# aKaReZa75_eBoard_STM32F103C8__STM32F103C.net
KiCad netlist of a schematic drawn in Altium Designer
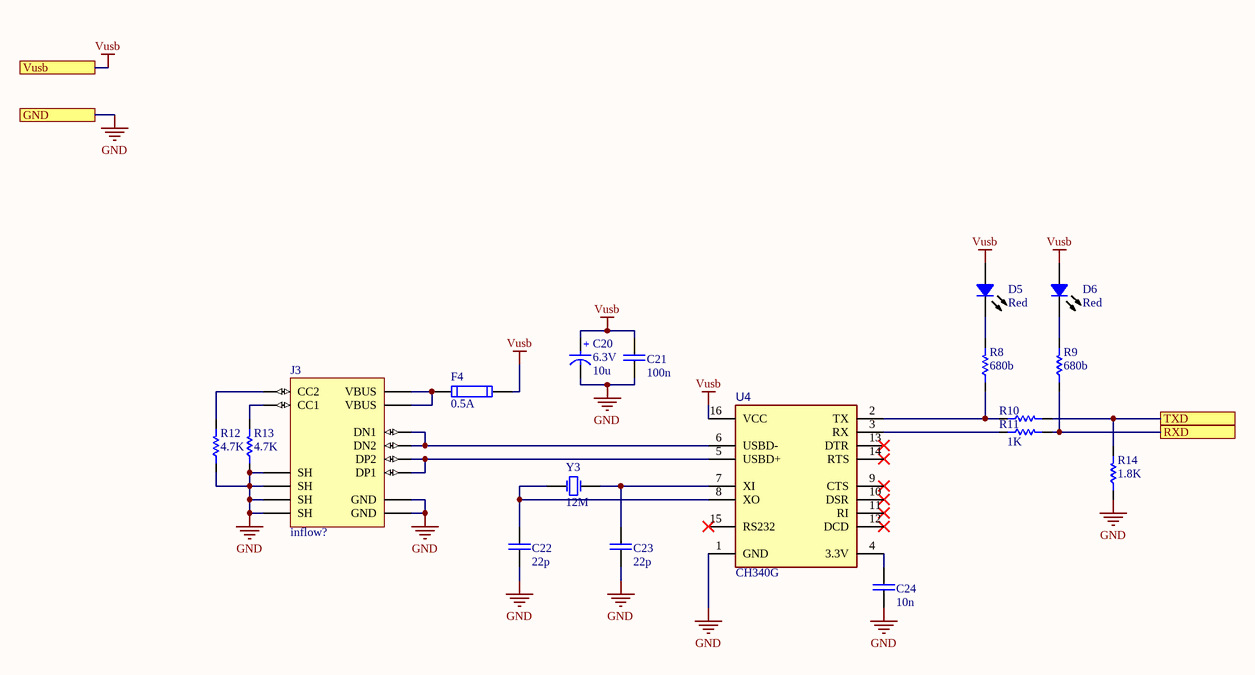
[diagram p0: aKaReZa75_eBoard_STM32F103C8__STM32F103C8__USBtoTTL.SchDoc]

(export (version "E")
  (design (tool "Eeschema 10.0.6"))
  (components
    (comp (ref "C20")
      (value "10u")
      (footprint "SMT_C_Tantalum_A")
      (description "Tantalum Capacitor,TAJ Series-SMD")
      (fields (field (name "RATING") "6.3V") (field (name "VALIDATION") "Valid"))
      (libsource (lib "aKaReZa") (part "Cap_Tantalum"))
    )
    (comp (ref "C21")
      (value "100n")
      (footprint "CAP 0805/2012")
      (description "Bipolar ceramic capacitor SMD")
      (fields (field (name "VALIDATION") "Valid"))
      (libsource (lib "aKaReZa") (part "Cap_Multi_SMD_100nF_0805"))
    )
    (comp (ref "C22")
      (value "22p")
      (footprint "CAP 0805/2012")
      (description "Bipolar ceramic capacitor SMD")
      (fields (field (name "VALIDATION") "Valid"))
      (libsource (lib "aKaReZa") (part "Cap_Multi_SMD_0805"))
    )
    (comp (ref "C23")
      (value "22p")
      (footprint "CAP 0805/2012")
      (description "Bipolar ceramic capacitor SMD")
      (fields (field (name "VALIDATION") "Valid"))
      (libsource (lib "aKaReZa") (part "Cap_Multi_SMD_0805"))
    )
    (comp (ref "C24")
      (value "10n")
      (footprint "CAP 0805/2012")
      (description "Bipolar ceramic capacitor SMD")
      (fields (field (name "VALIDATION") "Valid"))
      (libsource (lib "aKaReZa") (part "Cap_Multi_SMD_0805"))
    )
    (comp (ref "D5")
      (value "Red")
      (footprint "LED 0805/2012 RED")
      (description "LED")
      (fields (field (name "VALIDATION") "Valid"))
      (libsource (lib "aKaReZa") (part "Semi_LED_SMD"))
    )
    (comp (ref "D6")
      (value "Red")
      (footprint "LED 0805/2012 RED")
      (description "LED")
      (fields (field (name "VALIDATION") "Valid"))
      (libsource (lib "aKaReZa") (part "Semi_LED_SMD"))
    )
    (comp (ref "F4")
      (value "0.5A")
      (footprint "1206_F")
      (description "Short circiut  protection")
      (fields (field (name "VALIDATION") "Valid"))
      (libsource (lib "aKaReZa") (part "Other_Elec_Fuse_SMD"))
    )
    (comp (ref "J3")
      (value "12b")
      (footprint "HRO_TYPE-C-31-M-12 - Extended")
      (description "USB C Female Connector")
      (fields (field (name "INFLOW") "inflow?") (field (name "VALIDATION") "Valid"))
      (libsource (lib "aKaReZa") (part "Con_USB_C"))
    )
    (comp (ref "R8")
      (value "680b")
      (footprint "RES 0805 (2012X06L)")
      (description "Resistor")
      (fields (field (name "VALIDATION") "Valid"))
      (libsource (lib "aKaReZa") (part "Res_SMD_0805"))
    )
    (comp (ref "R9")
      (value "680b")
      (footprint "RES 0805 (2012X06L)")
      (description "Resistor")
      (fields (field (name "VALIDATION") "Valid"))
      (libsource (lib "aKaReZa") (part "Res_SMD_0805"))
    )
    (comp (ref "R10")
      (value "1K")
      (footprint "RES 0805 (2012X06L)")
      (description "Resistor")
      (fields (field (name "VALIDATION") "Valid"))
      (libsource (lib "aKaReZa") (part "Res_SMD_0805"))
    )
    (comp (ref "R11")
      (value "1K")
      (footprint "RES 0805 (2012X06L)")
      (description "Resistor")
      (fields (field (name "VALIDATION") "Valid"))
      (libsource (lib "aKaReZa") (part "Res_SMD_0805"))
    )
    (comp (ref "R12")
      (value "4.7K")
      (footprint "RES 0805 (2012X06L)")
      (description "Resistor")
      (fields (field (name "VALIDATION") "Valid"))
      (libsource (lib "aKaReZa") (part "Res_SMD_0805"))
    )
    (comp (ref "R13")
      (value "4.7K")
      (footprint "RES 0805 (2012X06L)")
      (description "Resistor")
      (fields (field (name "VALIDATION") "Valid"))
      (libsource (lib "aKaReZa") (part "Res_SMD_0805"))
    )
    (comp (ref "R14")
      (value "1.8K")
      (footprint "RES 0805 (2012X06L)")
      (description "Resistor")
      (fields (field (name "VALIDATION") "Valid"))
      (libsource (lib "aKaReZa") (part "Res_SMD_0805"))
    )
    (comp (ref "U4")
      (value "CH340G")
      (footprint "SO16_M")
      (description "TTL To USB Chip")
      (fields (field (name "VALIDATION") "Valid"))
      (libsource (lib "aKaReZa") (part "IC_Converter_CH340G"))
    )
    (comp (ref "Y3")
      (value "12M")
      (footprint "Crystal SMD")
      (description "Crystal Oscillator")
      (fields (field (name "VALIDATION") "Valid"))
      (libsource (lib "aKaReZa") (part "Other_Elec_Xtal_SMD"))
    )
  )
  (nets
    (net (code "1") (name "/RXD") (class "Default")
      (node (ref "R11") (pin "2") (pinfunction "2_2") (pintype "passive"))
      (node (ref "R9") (pin "1") (pinfunction "1_1") (pintype "passive"))
    )
    (net (code "2") (name "/TXD") (class "Default")
      (node (ref "R10") (pin "2") (pinfunction "2_2") (pintype "passive"))
      (node (ref "R14") (pin "2") (pinfunction "2_2") (pintype "passive"))
    )
    (net (code "3") (name "GND") (class "Default")
      (node (ref "C20") (pin "2") (pinfunction "-_2") (pintype "passive"))
      (node (ref "C21") (pin "2") (pinfunction "2_2") (pintype "passive"))
      (node (ref "C22") (pin "2") (pinfunction "2_2") (pintype "passive"))
      (node (ref "C23") (pin "2") (pinfunction "2_2") (pintype "passive"))
      (node (ref "C24") (pin "2") (pinfunction "2_2") (pintype "passive"))
      (node (ref "J3") (pin "A1_B12") (pinfunction "GND_A1_B12") (pintype "power_in"))
      (node (ref "J3") (pin "B1_A12") (pinfunction "GND_B1_A12") (pintype "power_in"))
      (node (ref "J3") (pin "S1") (pinfunction "SH_S1") (pintype "passive"))
      (node (ref "J3") (pin "S2") (pinfunction "SH_S2") (pintype "passive"))
      (node (ref "J3") (pin "S3") (pinfunction "SH_S3") (pintype "passive"))
      (node (ref "J3") (pin "S4") (pinfunction "SH_S4") (pintype "passive"))
      (node (ref "R12") (pin "1") (pinfunction "1_1") (pintype "passive"))
      (node (ref "R13") (pin "1") (pinfunction "1_1") (pintype "passive"))
      (node (ref "R14") (pin "1") (pinfunction "1_1") (pintype "passive"))
      (node (ref "U4") (pin "1") (pinfunction "GND_1") (pintype "passive"))
    )
    (net (code "4") (name "Net-(D5-Pad2)") (class "Default")
      (node (ref "D5") (pin "2") (pinfunction "2_2") (pintype "passive"))
      (node (ref "R8") (pin "2") (pinfunction "2_2") (pintype "passive"))
    )
    (net (code "5") (name "Net-(D6-Pad2)") (class "Default")
      (node (ref "D6") (pin "2") (pinfunction "2_2") (pintype "passive"))
      (node (ref "R9") (pin "2") (pinfunction "2_2") (pintype "passive"))
    )
    (net (code "6") (name "Net-(F4-Pad1)") (class "Default")
      (node (ref "F4") (pin "1") (pinfunction "1_1") (pintype "passive"))
      (node (ref "J3") (pin "A4_B9") (pinfunction "VBUS_A4_B9") (pintype "power_in"))
      (node (ref "J3") (pin "B4_A9") (pinfunction "VBUS_B4_A9") (pintype "power_in"))
    )
    (net (code "7") (name "Net-(J3-CC1)") (class "Default")
      (node (ref "J3") (pin "A5") (pinfunction "CC1_A5") (pintype "bidirectional"))
      (node (ref "R13") (pin "2") (pinfunction "2_2") (pintype "passive"))
    )
    (net (code "8") (name "Net-(J3-CC2)") (class "Default")
      (node (ref "J3") (pin "B5") (pinfunction "CC2_B5") (pintype "bidirectional"))
      (node (ref "R12") (pin "2") (pinfunction "2_2") (pintype "passive"))
    )
    (net (code "9") (name "Net-(J3-DN1)") (class "Default")
      (node (ref "J3") (pin "A7") (pinfunction "DN1_A7") (pintype "bidirectional"))
      (node (ref "J3") (pin "B7") (pinfunction "DN2_B7") (pintype "bidirectional"))
      (node (ref "U4") (pin "6") (pinfunction "USBD-_6") (pintype "passive"))
    )
    (net (code "10") (name "Net-(J3-DP1)") (class "Default")
      (node (ref "J3") (pin "A6") (pinfunction "DP1_A6") (pintype "bidirectional"))
      (node (ref "J3") (pin "B6") (pinfunction "DP2_B6") (pintype "bidirectional"))
      (node (ref "U4") (pin "5") (pinfunction "USBD+_5") (pintype "passive"))
    )
    (net (code "11") (name "Net-(U4-3.3V)") (class "Default")
      (node (ref "C24") (pin "1") (pinfunction "1_1") (pintype "passive"))
      (node (ref "U4") (pin "4") (pinfunction "3.3V_4") (pintype "passive"))
    )
    (net (code "12") (name "Net-(U4-RX)") (class "Default")
      (node (ref "R11") (pin "1") (pinfunction "1_1") (pintype "passive"))
      (node (ref "U4") (pin "3") (pinfunction "RX_3") (pintype "passive"))
    )
    (net (code "13") (name "Net-(U4-TX)") (class "Default")
      (node (ref "R10") (pin "1") (pinfunction "1_1") (pintype "passive"))
      (node (ref "R8") (pin "1") (pinfunction "1_1") (pintype "passive"))
      (node (ref "U4") (pin "2") (pinfunction "TX_2") (pintype "passive"))
    )
    (net (code "14") (name "Net-(U4-XI)") (class "Default")
      (node (ref "C23") (pin "1") (pinfunction "1_1") (pintype "passive"))
      (node (ref "U4") (pin "7") (pinfunction "XI_7") (pintype "passive"))
      (node (ref "Y3") (pin "2") (pinfunction "OSC2_2") (pintype "passive"))
    )
    (net (code "15") (name "Net-(U4-XO)") (class "Default")
      (node (ref "C22") (pin "1") (pinfunction "1_1") (pintype "passive"))
      (node (ref "U4") (pin "8") (pinfunction "XO_8") (pintype "passive"))
      (node (ref "Y3") (pin "1") (pinfunction "OSC1_1") (pintype "passive"))
    )
    (net (code "16") (name "Vusb") (class "Default")
      (node (ref "C20") (pin "1") (pinfunction "+_1") (pintype "passive"))
      (node (ref "C21") (pin "1") (pinfunction "1_1") (pintype "passive"))
      (node (ref "D5") (pin "1") (pinfunction "1_1") (pintype "passive"))
      (node (ref "D6") (pin "1") (pinfunction "1_1") (pintype "passive"))
      (node (ref "F4") (pin "2") (pinfunction "2_2") (pintype "passive"))
      (node (ref "U4") (pin "16") (pinfunction "VCC_16") (pintype "passive"))
    )
    (net (code "17") (name "unconnected-(U4-CTS-Pad9)") (class "Default")
      (node (ref "U4") (pin "9") (pinfunction "CTS_9") (pintype "passive+no_connect"))
    )
    (net (code "18") (name "unconnected-(U4-DCD-Pad12)") (class "Default")
      (node (ref "U4") (pin "12") (pinfunction "DCD_12") (pintype "passive+no_connect"))
    )
    (net (code "19") (name "unconnected-(U4-DSR-Pad10)") (class "Default")
      (node (ref "U4") (pin "10") (pinfunction "DSR_10") (pintype "passive+no_connect"))
    )
    (net (code "20") (name "unconnected-(U4-DTR-Pad13)") (class "Default")
      (node (ref "U4") (pin "13") (pinfunction "DTR_13") (pintype "passive+no_connect"))
    )
    (net (code "21") (name "unconnected-(U4-RI-Pad11)") (class "Default")
      (node (ref "U4") (pin "11") (pinfunction "RI_11") (pintype "passive+no_connect"))
    )
    (net (code "22") (name "unconnected-(U4-RS232-Pad15)") (class "Default")
      (node (ref "U4") (pin "15") (pinfunction "RS232_15") (pintype "passive+no_connect"))
    )
    (net (code "23") (name "unconnected-(U4-RTS-Pad14)") (class "Default")
      (node (ref "U4") (pin "14") (pinfunction "RTS_14") (pintype "passive+no_connect"))
    )
  )
)
